# Power.net
KiCad netlist of a schematic drawn in Altium Designer
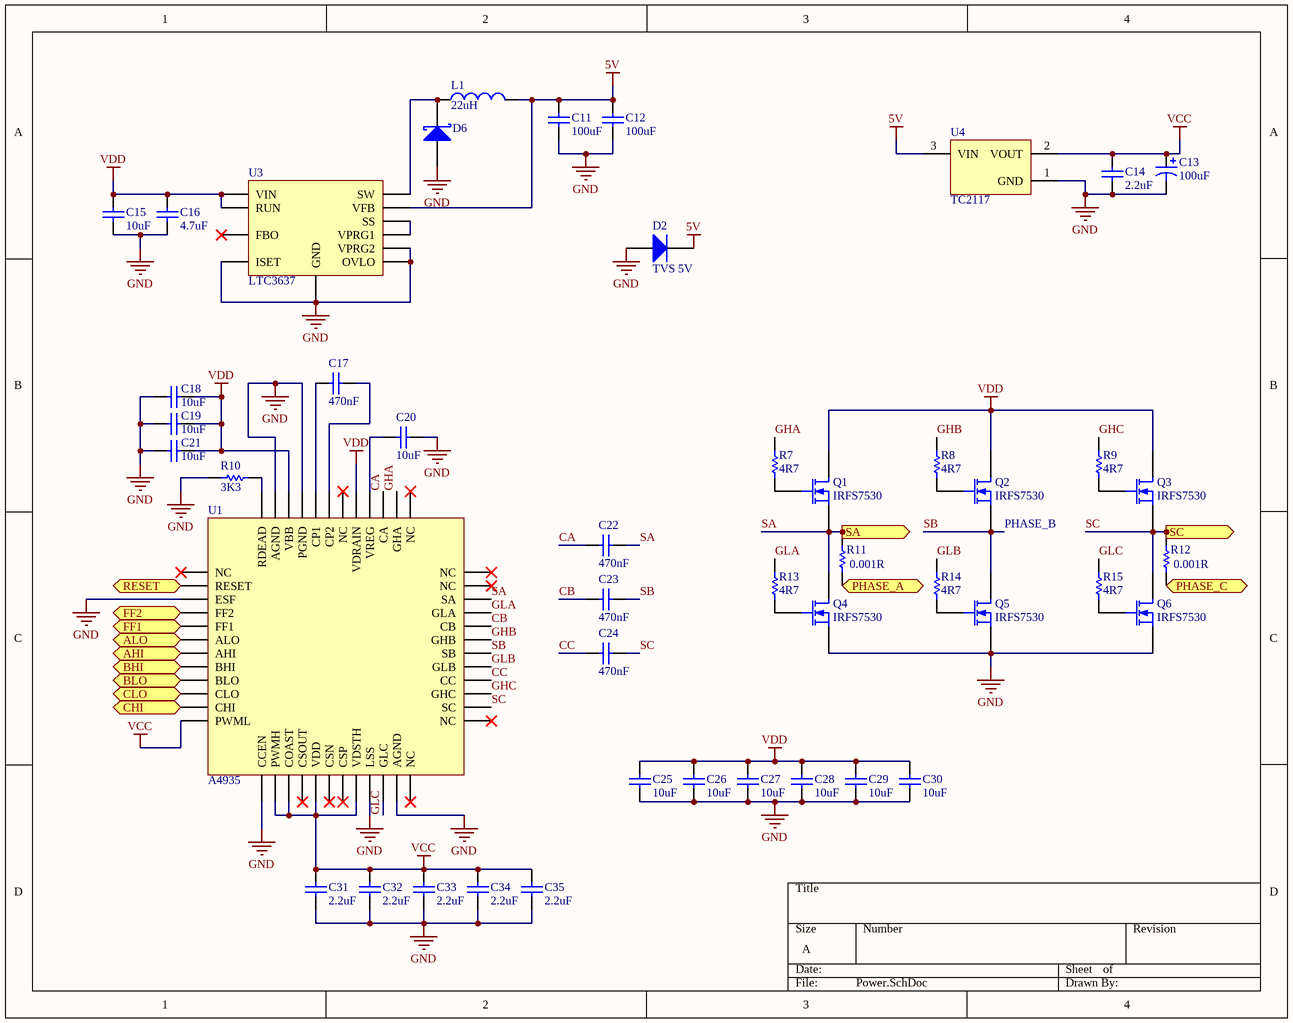
[diagram p0: Power.SchDoc]

(export (version "E")
  (design (tool "Eeschema 10.0.6"))
  (components
    (comp (ref "C11")
      (value "100uF")
      (footprint "CAPC1210(3225)280_N")
      (description "CAP 100uF 10V Â±10% 1210 (3225 Metric) Thickness 2.8mm SMD")
      (fields (field (name "TOLERANCE") "Â±10%"))
      (libsource (lib "Altium Content Vault") (part "CMP-1038-02301-1"))
    )
    (comp (ref "C12")
      (value "100uF")
      (footprint "CAPC1210(3225)280_N")
      (description "CAP 100uF 10V Â±10% 1210 (3225 Metric) Thickness 2.8mm SMD")
      (fields (field (name "TOLERANCE") "Â±10%"))
      (libsource (lib "Altium Content Vault") (part "CMP-1038-02301-1"))
    )
    (comp (ref "C13")
      (value "100uF")
      (footprint "AVX-CAPC7343_V")
      (libsource (lib "Components") (part "AVX-CAP-P-2"))
    )
    (comp (ref "C14")
      (value "2.2uF")
      (footprint "CAPC0603(1608)55_N")
      (description "CAP 2.2uF 16V Â±10% 0603 (1608 Metric) Thickness 0.55mm SMD")
      (fields (field (name "TOLERANCE") "Â±10%"))
      (libsource (lib "Altium Content Vault") (part "CMP-1035-02762-1"))
    )
    (comp (ref "C15")
      (value "10uF")
      (footprint "CAPC1206(3216)190_M")
      (description "CAP 10uF 50V Â±10% 1206 (3216 Metric) Thickness 1.9mm SMD")
      (fields (field (name "TOLERANCE") "Â±10%"))
      (libsource (lib "Altium Content Vault") (part "CAP"))
    )
    (comp (ref "C16")
      (value "4.7uF")
      (footprint "CAPC0805(2012)145_N")
      (description "CAP 4.7uF 50V Â±10% 0805 (2012 Metric) Thickness 1.45mm SMD")
      (fields (field (name "TOLERANCE") "Â±10%"))
      (libsource (lib "Altium Content Vault") (part "CAP"))
    )
    (comp (ref "C17")
      (value "470nF")
      (footprint "CAPC0603(1608)100_N")
      (description "CAP 470nF 25V Â±20% 0603 (1608 Metric) Thickness 1mm SMD")
      (fields (field (name "TOLERANCE") "Â±20%"))
      (libsource (lib "Altium Content Vault") (part "CAP"))
    )
    (comp (ref "C18")
      (value "10uF")
      (footprint "CAPC1206(3216)190_M")
      (description "CAP 10uF 50V Â±10% 1206 (3216 Metric) Thickness 1.9mm SMD")
      (fields (field (name "TOLERANCE") "Â±10%"))
      (libsource (lib "Altium Content Vault") (part "CAP"))
    )
    (comp (ref "C19")
      (value "10uF")
      (footprint "CAPC1206(3216)190_M")
      (description "CAP 10uF 50V Â±10% 1206 (3216 Metric) Thickness 1.9mm SMD")
      (fields (field (name "TOLERANCE") "Â±10%"))
      (libsource (lib "Altium Content Vault") (part "CAP"))
    )
    (comp (ref "C20")
      (value "10uF")
      (footprint "CAPC0805(2012)145_N")
      (description "CAP 10uF 25V Â±10% 0805 (2012 Metric) Thickness 1.45mm SMD")
      (fields (field (name "TOLERANCE") "Â±10%"))
      (libsource (lib "Altium Content Vault") (part "CAP"))
    )
    (comp (ref "C21")
      (value "10uF")
      (footprint "CAPC1206(3216)190_M")
      (description "CAP 10uF 50V Â±10% 1206 (3216 Metric) Thickness 1.9mm SMD")
      (fields (field (name "TOLERANCE") "Â±10%"))
      (libsource (lib "Altium Content Vault") (part "CAP"))
    )
    (comp (ref "C22")
      (value "470nF")
      (footprint "CAPC0603(1608)100_L")
      (description "CAP 470nF 25V Â±10% 0603 (1608 Metric) Thickness 1mm SMD")
      (fields (field (name "TOLERANCE") "Â±10%"))
      (libsource (lib "Altium Content Vault") (part "CAP"))
    )
    (comp (ref "C23")
      (value "470nF")
      (footprint "CAPC0603(1608)100_L")
      (description "CAP 470nF 25V Â±10% 0603 (1608 Metric) Thickness 1mm SMD")
      (fields (field (name "TOLERANCE") "Â±10%"))
      (libsource (lib "Altium Content Vault") (part "CAP"))
    )
    (comp (ref "C24")
      (value "470nF")
      (footprint "CAPC0603(1608)100_L")
      (description "CAP 470nF 25V Â±10% 0603 (1608 Metric) Thickness 1mm SMD")
      (fields (field (name "TOLERANCE") "Â±10%"))
      (libsource (lib "Altium Content Vault") (part "CAP"))
    )
    (comp (ref "C25")
      (value "10uF")
      (footprint "CAPC1206(3216)190_M")
      (description "CAP 10uF 50V Â±10% 1206 (3216 Metric) Thickness 1.9mm SMD")
      (fields (field (name "TOLERANCE") "Â±10%"))
      (libsource (lib "Altium Content Vault") (part "CMP-1037-04982-1"))
    )
    (comp (ref "C26")
      (value "10uF")
      (footprint "CAPC1206(3216)190_M")
      (description "CAP 10uF 50V Â±10% 1206 (3216 Metric) Thickness 1.9mm SMD")
      (fields (field (name "TOLERANCE") "Â±10%"))
      (libsource (lib "Altium Content Vault") (part "CAP"))
    )
    (comp (ref "C27")
      (value "10uF")
      (footprint "CAPC1206(3216)190_M")
      (description "CAP 10uF 50V Â±10% 1206 (3216 Metric) Thickness 1.9mm SMD")
      (fields (field (name "TOLERANCE") "Â±10%"))
      (libsource (lib "Altium Content Vault") (part "CAP"))
    )
    (comp (ref "C28")
      (value "10uF")
      (footprint "CAPC1206(3216)190_M")
      (description "CAP 10uF 50V Â±10% 1206 (3216 Metric) Thickness 1.9mm SMD")
      (fields (field (name "TOLERANCE") "Â±10%"))
      (libsource (lib "Altium Content Vault") (part "CMP-1037-04982-1"))
    )
    (comp (ref "C29")
      (value "10uF")
      (footprint "CAPC1206(3216)190_M")
      (description "CAP 10uF 50V Â±10% 1206 (3216 Metric) Thickness 1.9mm SMD")
      (fields (field (name "TOLERANCE") "Â±10%"))
      (libsource (lib "Altium Content Vault") (part "CAP"))
    )
    (comp (ref "C30")
      (value "10uF")
      (footprint "CAPC1206(3216)190_M")
      (description "CAP 10uF 50V Â±10% 1206 (3216 Metric) Thickness 1.9mm SMD")
      (fields (field (name "TOLERANCE") "Â±10%"))
      (libsource (lib "Altium Content Vault") (part "CAP"))
    )
    (comp (ref "C31")
      (value "2.2uF")
      (footprint "CAPC0603(1608)55_N")
      (description "CAP 2.2uF 16V Â±10% 0603 (1608 Metric) Thickness 0.55mm SMD")
      (fields (field (name "TOLERANCE") "Â±10%"))
      (libsource (lib "Altium Content Vault") (part "CMP-1035-02762-1"))
    )
    (comp (ref "C32")
      (value "2.2uF")
      (footprint "CAPC0603(1608)55_N")
      (description "CAP 2.2uF 16V Â±10% 0603 (1608 Metric) Thickness 0.55mm SMD")
      (fields (field (name "TOLERANCE") "Â±10%"))
      (libsource (lib "Altium Content Vault") (part "CMP-1035-02762-1"))
    )
    (comp (ref "C33")
      (value "2.2uF")
      (footprint "CAPC0603(1608)55_N")
      (description "CAP 2.2uF 16V Â±10% 0603 (1608 Metric) Thickness 0.55mm SMD")
      (fields (field (name "TOLERANCE") "Â±10%"))
      (libsource (lib "Altium Content Vault") (part "CMP-1035-02762-1"))
    )
    (comp (ref "C34")
      (value "2.2uF")
      (footprint "CAPC0603(1608)55_N")
      (description "CAP 2.2uF 16V Â±10% 0603 (1608 Metric) Thickness 0.55mm SMD")
      (fields (field (name "TOLERANCE") "Â±10%"))
      (libsource (lib "Altium Content Vault") (part "CMP-1035-02762-1"))
    )
    (comp (ref "C35")
      (value "2.2uF")
      (footprint "CAPC0603(1608)55_N")
      (description "CAP 2.2uF 16V Â±10% 0603 (1608 Metric) Thickness 0.55mm SMD")
      (fields (field (name "TOLERANCE") "Â±10%"))
      (libsource (lib "Altium Content Vault") (part "CMP-1035-02762-1"))
    )
    (comp (ref "D2")
      (value "TVS 5V")
      (footprint "VISH-DO-214AC-2_N")
      (fields
        (field (name "PARTNUMBER") "SMAJ5.0A-E3/61")
        (field (name "MANUFACTURER") "Vishay Semiconductor")
      )
      (libsource (lib "Altium Content Vault") (part "CMP-0548-00235-1"))
    )
    (comp (ref "D6")
      (value "~")
      (footprint "SMB")
      (description "Schottky Diode")
      (fields (field (name "PUBLISHER") "Altium Limited"))
      (libsource (lib "Miscellaneous Devices") (part "D Schottky"))
    )
    (comp (ref "L1")
      (value "22uH")
      (footprint "SDR0805-180ML")
      (description "Inductor")
      (fields (field (name "Comment") "SDR0805-180ML") (field (name "PUBLISHER") "Altium Limited"))
      (libsource (lib "Components") (part "SDR0805-180ML"))
    )
    (comp (ref "Q1")
      (value "IRFS7530")
      (footprint "DPAK127P1525X483-7N")
      (description "N-Channel MOSFET")
      (fields (field (name "PUBLISHER") "Altium Limited"))
      (libsource (lib "Components") (part "IRFS7530"))
    )
    (comp (ref "Q2")
      (value "IRFS7530")
      (footprint "DPAK127P1525X483-7N")
      (description "N-Channel MOSFET")
      (fields (field (name "PUBLISHER") "Altium Limited"))
      (libsource (lib "Components") (part "IRFS7530"))
    )
    (comp (ref "Q3")
      (value "IRFS7530")
      (footprint "DPAK127P1525X483-7N")
      (description "N-Channel MOSFET")
      (fields (field (name "PUBLISHER") "Altium Limited"))
      (libsource (lib "Components") (part "IRFS7530"))
    )
    (comp (ref "Q4")
      (value "IRFS7530")
      (footprint "DPAK127P1525X483-7N")
      (description "N-Channel MOSFET")
      (fields (field (name "PUBLISHER") "Altium Limited"))
      (libsource (lib "Components") (part "IRFS7530"))
    )
    (comp (ref "Q5")
      (value "IRFS7530")
      (footprint "DPAK127P1525X483-7N")
      (description "N-Channel MOSFET")
      (fields (field (name "PUBLISHER") "Altium Limited"))
      (libsource (lib "Components") (part "IRFS7530"))
    )
    (comp (ref "Q6")
      (value "IRFS7530")
      (footprint "DPAK127P1525X483-7N")
      (description "N-Channel MOSFET")
      (fields (field (name "PUBLISHER") "Altium Limited"))
      (libsource (lib "Components") (part "IRFS7530"))
    )
    (comp (ref "R7")
      (value "4R7")
      (footprint "RESC0603(1608)_N")
      (description "4R7 0.1W 5% 0603 (1608 Metric)  SMD")
      (fields (field (name "POWER") "0.1 W") (field (name "TOLERANCE") "5 %"))
      (libsource (lib "Altium Content Vault") (part "CMP-1012-00018-1"))
    )
    (comp (ref "R8")
      (value "4R7")
      (footprint "RESC0603(1608)_N")
      (description "4R7 0.1W 5% 0603 (1608 Metric)  SMD")
      (fields (field (name "POWER") "0.1 W") (field (name "TOLERANCE") "5 %"))
      (libsource (lib "Altium Content Vault") (part "CMP-1012-00018-1"))
    )
    (comp (ref "R9")
      (value "4R7")
      (footprint "RESC0603(1608)_N")
      (description "4R7 0.1W 5% 0603 (1608 Metric)  SMD")
      (fields (field (name "POWER") "0.1 W") (field (name "TOLERANCE") "5 %"))
      (libsource (lib "Altium Content Vault") (part "CMP-1012-00018-1"))
    )
    (comp (ref "R10")
      (value "3K3")
      (footprint "RESC0603(1608)_N")
      (description "3K3 0.1W 5% 0603 (1608 Metric)  SMD")
      (fields (field (name "TOLERANCE") "5 %") (field (name "POWER") "0.1 W"))
      (libsource (lib "Altium Content Vault") (part "CMP-1012-00086-1"))
    )
    (comp (ref "R11")
      (value "0.001R")
      (footprint "Shunt")
      (fields (field (name "PUBLISHER") "Altium Limited"))
      (libsource (lib "Components") (part "Shunt"))
    )
    (comp (ref "R12")
      (value "0.001R")
      (footprint "Shunt")
      (description "Resistor")
      (fields (field (name "PUBLISHER") "Altium Limited"))
      (libsource (lib "Components") (part "Shunt"))
    )
    (comp (ref "R13")
      (value "4R7")
      (footprint "RESC0603(1608)_N")
      (description "4R7 0.1W 5% 0603 (1608 Metric)  SMD")
      (fields (field (name "POWER") "0.1 W") (field (name "TOLERANCE") "5 %"))
      (libsource (lib "Altium Content Vault") (part "CMP-1012-00018-1"))
    )
    (comp (ref "R14")
      (value "4R7")
      (footprint "RESC0603(1608)_N")
      (description "4R7 0.1W 5% 0603 (1608 Metric)  SMD")
      (fields (field (name "POWER") "0.1 W") (field (name "TOLERANCE") "5 %"))
      (libsource (lib "Altium Content Vault") (part "CMP-1012-00018-1"))
    )
    (comp (ref "R15")
      (value "4R7")
      (footprint "RESC0603(1608)_N")
      (description "4R7 0.1W 5% 0603 (1608 Metric)  SMD")
      (fields (field (name "POWER") "0.1 W") (field (name "TOLERANCE") "5 %"))
      (libsource (lib "Altium Content Vault") (part "CMP-1012-00018-1"))
    )
    (comp (ref "U1") (value "A4935") (footprint "LQFP-48") (libsource (lib "Components") (part "A4935")))
    (comp (ref "U3")
      (value "LTC3637")
      (footprint "SON50P300X85_HS-17N")
      (libsource (lib "Components") (part "LTC3637"))
    )
    (comp (ref "U4")
      (value "TC2117")
      (footprint "SOT-223-DB3_M")
      (libsource (lib "Components") (part "PM-LINEREG-TC2117-IL4"))
    )
  )
  (nets
    (net (code "1") (name "/AHI") (class "Default")
      (node (ref "U1") (pin "7") (pinfunction "AHI_7") (pintype "passive"))
    )
    (net (code "2") (name "/ALO") (class "Default")
      (node (ref "U1") (pin "6") (pinfunction "ALO_6") (pintype "passive"))
    )
    (net (code "3") (name "/BHI") (class "Default")
      (node (ref "U1") (pin "8") (pinfunction "BHI_8") (pintype "passive"))
    )
    (net (code "4") (name "/BLO") (class "Default")
      (node (ref "U1") (pin "9") (pinfunction "BLO_9") (pintype "passive"))
    )
    (net (code "5") (name "/CA") (class "Default")
      (node (ref "C22") (pin "1") (pinfunction "1_1") (pintype "passive"))
      (node (ref "U1") (pin "39") (pinfunction "CA_39") (pintype "passive"))
    )
    (net (code "6") (name "/CB") (class "Default")
      (node (ref "C23") (pin "1") (pinfunction "1_1") (pintype "passive"))
      (node (ref "U1") (pin "32") (pinfunction "CB_32") (pintype "passive"))
    )
    (net (code "7") (name "/CC") (class "Default")
      (node (ref "C24") (pin "1") (pinfunction "1_1") (pintype "passive"))
      (node (ref "U1") (pin "28") (pinfunction "CC_28") (pintype "passive"))
    )
    (net (code "8") (name "/CHI") (class "Default")
      (node (ref "U1") (pin "11") (pinfunction "CHI_11") (pintype "passive"))
    )
    (net (code "9") (name "/CLO") (class "Default")
      (node (ref "U1") (pin "10") (pinfunction "CLO_10") (pintype "passive"))
    )
    (net (code "10") (name "/FF1") (class "Default")
      (node (ref "U1") (pin "5") (pinfunction "FF1_5") (pintype "passive"))
    )
    (net (code "11") (name "/FF2") (class "Default")
      (node (ref "U1") (pin "4") (pinfunction "FF2_4") (pintype "passive"))
    )
    (net (code "12") (name "/GHA") (class "Default")
      (node (ref "R7") (pin "2") (pinfunction "2_2") (pintype "passive"))
      (node (ref "U1") (pin "38") (pinfunction "GHA_38") (pintype "passive"))
    )
    (net (code "13") (name "/GHB") (class "Default")
      (node (ref "R8") (pin "2") (pinfunction "2_2") (pintype "passive"))
      (node (ref "U1") (pin "31") (pinfunction "GHB_31") (pintype "passive"))
    )
    (net (code "14") (name "/GHC") (class "Default")
      (node (ref "R9") (pin "2") (pinfunction "2_2") (pintype "passive"))
      (node (ref "U1") (pin "27") (pinfunction "GHC_27") (pintype "passive"))
    )
    (net (code "15") (name "/GLA") (class "Default")
      (node (ref "R13") (pin "2") (pinfunction "2_2") (pintype "passive"))
      (node (ref "U1") (pin "33") (pinfunction "GLA_33") (pintype "passive"))
    )
    (net (code "16") (name "/GLB") (class "Default")
      (node (ref "R14") (pin "2") (pinfunction "2_2") (pintype "passive"))
      (node (ref "U1") (pin "29") (pinfunction "GLB_29") (pintype "passive"))
    )
    (net (code "17") (name "/GLC") (class "Default")
      (node (ref "R15") (pin "2") (pinfunction "2_2") (pintype "passive"))
      (node (ref "U1") (pin "22") (pinfunction "GLC_22") (pintype "passive"))
    )
    (net (code "18") (name "/PHASE_A") (class "Default")
      (node (ref "R11") (pin "1") (pinfunction "1_1") (pintype "passive"))
    )
    (net (code "19") (name "/PHASE_C") (class "Default")
      (node (ref "R12") (pin "1") (pinfunction "1_1") (pintype "passive"))
    )
    (net (code "20") (name "/RESET") (class "Default")
      (node (ref "U1") (pin "2") (pinfunction "RESET_2") (pintype "passive"))
    )
    (net (code "21") (name "/SA") (class "Default")
      (node (ref "C22") (pin "2") (pinfunction "2_2") (pintype "passive"))
      (node (ref "Q1") (pin "3") (pinfunction "S_3") (pintype "passive"))
      (node (ref "Q4") (pin "1") (pinfunction "D_1") (pintype "passive"))
      (node (ref "R11") (pin "2") (pinfunction "2_2") (pintype "passive"))
      (node (ref "U1") (pin "34") (pinfunction "SA_34") (pintype "passive"))
    )
    (net (code "22") (name "/SB") (class "Default")
      (node (ref "C23") (pin "2") (pinfunction "2_2") (pintype "passive"))
      (node (ref "Q2") (pin "3") (pinfunction "S_3") (pintype "passive"))
      (node (ref "Q5") (pin "1") (pinfunction "D_1") (pintype "passive"))
      (node (ref "U1") (pin "30") (pinfunction "SB_30") (pintype "passive"))
    )
    (net (code "23") (name "/SC") (class "Default")
      (node (ref "C24") (pin "2") (pinfunction "2_2") (pintype "passive"))
      (node (ref "Q3") (pin "3") (pinfunction "S_3") (pintype "passive"))
      (node (ref "Q6") (pin "1") (pinfunction "D_1") (pintype "passive"))
      (node (ref "R12") (pin "2") (pinfunction "2_2") (pintype "passive"))
      (node (ref "U1") (pin "26") (pinfunction "SC_26") (pintype "passive"))
    )
    (net (code "24") (name "5V") (class "Default")
      (node (ref "C11") (pin "2") (pinfunction "2_2") (pintype "passive"))
      (node (ref "C12") (pin "2") (pinfunction "2_2") (pintype "passive"))
      (node (ref "D2") (pin "1") (pinfunction "K_1") (pintype "passive"))
      (node (ref "L1") (pin "2") (pinfunction "2_2") (pintype "passive"))
      (node (ref "U3") (pin "9") (pinfunction "VFB_9") (pintype "passive"))
      (node (ref "U4") (pin "3") (pinfunction "VIN_3") (pintype "power_in"))
    )
    (net (code "25") (name "GND") (class "Default")
      (node (ref "C11") (pin "1") (pinfunction "1_1") (pintype "passive"))
      (node (ref "C12") (pin "1") (pinfunction "1_1") (pintype "passive"))
      (node (ref "C13") (pin "2") (pinfunction "2_2") (pintype "passive"))
      (node (ref "C14") (pin "2") (pinfunction "2_2") (pintype "passive"))
      (node (ref "C15") (pin "1") (pinfunction "1_1") (pintype "passive"))
      (node (ref "C16") (pin "1") (pinfunction "1_1") (pintype "passive"))
      (node (ref "C18") (pin "1") (pinfunction "1_1") (pintype "passive"))
      (node (ref "C19") (pin "1") (pinfunction "1_1") (pintype "passive"))
      (node (ref "C20") (pin "2") (pinfunction "2_2") (pintype "passive"))
      (node (ref "C21") (pin "1") (pinfunction "1_1") (pintype "passive"))
      (node (ref "C25") (pin "1") (pinfunction "1_1") (pintype "passive"))
      (node (ref "C26") (pin "1") (pinfunction "1_1") (pintype "passive"))
      (node (ref "C27") (pin "1") (pinfunction "1_1") (pintype "passive"))
      (node (ref "C28") (pin "1") (pinfunction "1_1") (pintype "passive"))
      (node (ref "C29") (pin "1") (pinfunction "1_1") (pintype "passive"))
      (node (ref "C30") (pin "1") (pinfunction "1_1") (pintype "passive"))
      (node (ref "C31") (pin "1") (pinfunction "1_1") (pintype "passive"))
      (node (ref "C32") (pin "1") (pinfunction "1_1") (pintype "passive"))
      (node (ref "C33") (pin "1") (pinfunction "1_1") (pintype "passive"))
      (node (ref "C34") (pin "1") (pinfunction "1_1") (pintype "passive"))
      (node (ref "C35") (pin "1") (pinfunction "1_1") (pintype "passive"))
      (node (ref "D2") (pin "2") (pinfunction "A_2") (pintype "passive"))
      (node (ref "D6") (pin "1") (pinfunction "A_1") (pintype "passive"))
      (node (ref "Q4") (pin "3") (pinfunction "S_3") (pintype "passive"))
      (node (ref "Q5") (pin "3") (pinfunction "S_3") (pintype "passive"))
      (node (ref "Q6") (pin "3") (pinfunction "S_3") (pintype "passive"))
      (node (ref "R10") (pin "1") (pinfunction "1_1") (pintype "passive"))
      (node (ref "U1") (pin "13") (pinfunction "CCEN_13") (pintype "passive"))
      (node (ref "U1") (pin "21") (pinfunction "LSS_21") (pintype "passive"))
      (node (ref "U1") (pin "23") (pinfunction "AGND_23") (pintype "passive"))
      (node (ref "U1") (pin "3") (pinfunction "ESF_3") (pintype "passive"))
      (node (ref "U1") (pin "45") (pinfunction "PGND_45") (pintype "passive"))
      (node (ref "U1") (pin "47") (pinfunction "AGND_47") (pintype "passive"))
      (node (ref "U3") (pin "11") (pinfunction "ISET_11") (pintype "passive"))
      (node (ref "U3") (pin "12") (pinfunction "OVLO_12") (pintype "passive"))
      (node (ref "U3") (pin "17") (pinfunction "GND_17") (pintype "passive"))
      (node (ref "U3") (pin "6") (pinfunction "VPRG2_6") (pintype "passive"))
      (node (ref "U4") (pin "1") (pinfunction "GND_1") (pintype "power_in"))
    )
    (net (code "26") (name "Net-(D6-K)") (class "Default")
      (node (ref "D6") (pin "2") (pinfunction "K_2") (pintype "passive"))
      (node (ref "L1") (pin "1") (pinfunction "1_1") (pintype "passive"))
      (node (ref "U3") (pin "1") (pinfunction "SW_1") (pintype "passive"))
    )
    (net (code "27") (name "Net-(Q1-G)") (class "Default")
      (node (ref "Q1") (pin "2") (pinfunction "G_2") (pintype "passive"))
      (node (ref "R7") (pin "1") (pinfunction "1_1") (pintype "passive"))
    )
    (net (code "28") (name "Net-(Q2-G)") (class "Default")
      (node (ref "Q2") (pin "2") (pinfunction "G_2") (pintype "passive"))
      (node (ref "R8") (pin "1") (pinfunction "1_1") (pintype "passive"))
    )
    (net (code "29") (name "Net-(Q3-G)") (class "Default")
      (node (ref "Q3") (pin "2") (pinfunction "G_2") (pintype "passive"))
      (node (ref "R9") (pin "1") (pinfunction "1_1") (pintype "passive"))
    )
    (net (code "30") (name "Net-(Q4-G)") (class "Default")
      (node (ref "Q4") (pin "2") (pinfunction "G_2") (pintype "passive"))
      (node (ref "R13") (pin "1") (pinfunction "1_1") (pintype "passive"))
    )
    (net (code "31") (name "Net-(Q5-G)") (class "Default")
      (node (ref "Q5") (pin "2") (pinfunction "G_2") (pintype "passive"))
      (node (ref "R14") (pin "1") (pinfunction "1_1") (pintype "passive"))
    )
    (net (code "32") (name "Net-(Q6-G)") (class "Default")
      (node (ref "Q6") (pin "2") (pinfunction "G_2") (pintype "passive"))
      (node (ref "R15") (pin "1") (pinfunction "1_1") (pintype "passive"))
    )
    (net (code "33") (name "Net-(U1-CP1)") (class "Default")
      (node (ref "C17") (pin "1") (pinfunction "1_1") (pintype "passive"))
      (node (ref "U1") (pin "44") (pinfunction "CP1_44") (pintype "passive"))
    )
    (net (code "34") (name "Net-(U1-CP2)") (class "Default")
      (node (ref "C17") (pin "2") (pinfunction "2_2") (pintype "passive"))
      (node (ref "U1") (pin "43") (pinfunction "CP2_43") (pintype "passive"))
    )
    (net (code "35") (name "Net-(U1-RDEAD)") (class "Default")
      (node (ref "R10") (pin "2") (pinfunction "2_2") (pintype "passive"))
      (node (ref "U1") (pin "48") (pinfunction "RDEAD_48") (pintype "passive"))
    )
    (net (code "36") (name "Net-(U1-VREG)") (class "Default")
      (node (ref "C20") (pin "1") (pinfunction "1_1") (pintype "passive"))
      (node (ref "U1") (pin "40") (pinfunction "VREG_40") (pintype "passive"))
    )
    (net (code "37") (name "Net-(U3-SS)") (class "Default")
      (node (ref "U3") (pin "10") (pinfunction "SS_10") (pintype "passive"))
      (node (ref "U3") (pin "7") (pinfunction "VPRG1_7") (pintype "passive"))
    )
    (net (code "38") (name "VCC") (class "Default")
      (node (ref "C13") (pin "1") (pinfunction "1_1") (pintype "passive"))
      (node (ref "C14") (pin "1") (pinfunction "1_1") (pintype "passive"))
      (node (ref "C31") (pin "2") (pinfunction "2_2") (pintype "passive"))
      (node (ref "C32") (pin "2") (pinfunction "2_2") (pintype "passive"))
      (node (ref "C33") (pin "2") (pinfunction "2_2") (pintype "passive"))
      (node (ref "C34") (pin "2") (pinfunction "2_2") (pintype "passive"))
      (node (ref "C35") (pin "2") (pinfunction "2_2") (pintype "passive"))
      (node (ref "U1") (pin "12") (pinfunction "PWML_12") (pintype "passive"))
      (node (ref "U1") (pin "14") (pinfunction "PWMH_14") (pintype "passive"))
      (node (ref "U1") (pin "15") (pinfunction "COAST_15") (pintype "passive"))
      (node (ref "U1") (pin "17") (pinfunction "VDD_17") (pintype "passive"))
      (node (ref "U1") (pin "20") (pinfunction "VDSTH_20") (pintype "passive"))
      (node (ref "U4") (pin "2") (pinfunction "VOUT_2") (pintype "power_in"))
    )
    (net (code "39") (name "VDD") (class "Default")
      (node (ref "C15") (pin "2") (pinfunction "2_2") (pintype "passive"))
      (node (ref "C16") (pin "2") (pinfunction "2_2") (pintype "passive"))
      (node (ref "C18") (pin "2") (pinfunction "2_2") (pintype "passive"))
      (node (ref "C19") (pin "2") (pinfunction "2_2") (pintype "passive"))
      (node (ref "C21") (pin "2") (pinfunction "2_2") (pintype "passive"))
      (node (ref "C25") (pin "2") (pinfunction "2_2") (pintype "passive"))
      (node (ref "C26") (pin "2") (pinfunction "2_2") (pintype "passive"))
      (node (ref "C27") (pin "2") (pinfunction "2_2") (pintype "passive"))
      (node (ref "C28") (pin "2") (pinfunction "2_2") (pintype "passive"))
      (node (ref "C29") (pin "2") (pinfunction "2_2") (pintype "passive"))
      (node (ref "C30") (pin "2") (pinfunction "2_2") (pintype "passive"))
      (node (ref "Q1") (pin "1") (pinfunction "D_1") (pintype "passive"))
      (node (ref "Q2") (pin "1") (pinfunction "D_1") (pintype "passive"))
      (node (ref "Q3") (pin "1") (pinfunction "D_1") (pintype "passive"))
      (node (ref "U1") (pin "41") (pinfunction "VDRAIN_41") (pintype "passive"))
      (node (ref "U1") (pin "46") (pinfunction "VBB_46") (pintype "passive"))
      (node (ref "U3") (pin "14") (pinfunction "RUN_14") (pintype "passive"))
      (node (ref "U3") (pin "3") (pinfunction "VIN_3") (pintype "passive"))
    )
    (net (code "40") (name "unconnected-(U1-CSN-Pad18)") (class "Default")
      (node (ref "U1") (pin "18") (pinfunction "CSN_18") (pintype "passive+no_connect"))
    )
    (net (code "41") (name "unconnected-(U1-CSOUT-Pad16)") (class "Default")
      (node (ref "U1") (pin "16") (pinfunction "CSOUT_16") (pintype "passive+no_connect"))
    )
    (net (code "42") (name "unconnected-(U1-CSP-Pad19)") (class "Default")
      (node (ref "U1") (pin "19") (pinfunction "CSP_19") (pintype "passive+no_connect"))
    )
    (net (code "43") (name "unconnected-(U1-NC-Pad1)") (class "Default")
      (node (ref "U1") (pin "1") (pinfunction "NC_1") (pintype "passive+no_connect"))
    )
    (net (code "44") (name "unconnected-(U1-NC-Pad24)") (class "Default")
      (node (ref "U1") (pin "24") (pinfunction "NC_24") (pintype "passive+no_connect"))
    )
    (net (code "45") (name "unconnected-(U1-NC-Pad25)") (class "Default")
      (node (ref "U1") (pin "25") (pinfunction "NC_25") (pintype "passive+no_connect"))
    )
    (net (code "46") (name "unconnected-(U1-NC-Pad35)") (class "Default")
      (node (ref "U1") (pin "35") (pinfunction "NC_35") (pintype "passive+no_connect"))
    )
    (net (code "47") (name "unconnected-(U1-NC-Pad36)") (class "Default")
      (node (ref "U1") (pin "36") (pinfunction "NC_36") (pintype "passive+no_connect"))
    )
    (net (code "48") (name "unconnected-(U1-NC-Pad37)") (class "Default")
      (node (ref "U1") (pin "37") (pinfunction "NC_37") (pintype "passive+no_connect"))
    )
    (net (code "49") (name "unconnected-(U1-NC-Pad42)") (class "Default")
      (node (ref "U1") (pin "42") (pinfunction "NC_42") (pintype "passive+no_connect"))
    )
    (net (code "50") (name "unconnected-(U3-FBO-Pad5)") (class "Default")
      (node (ref "U3") (pin "5") (pinfunction "FBO_5") (pintype "passive+no_connect"))
    )
  )
)
